# Small_Vitals_2021-03-09.net
KiCad netlist of a schematic drawn in EasyEDA
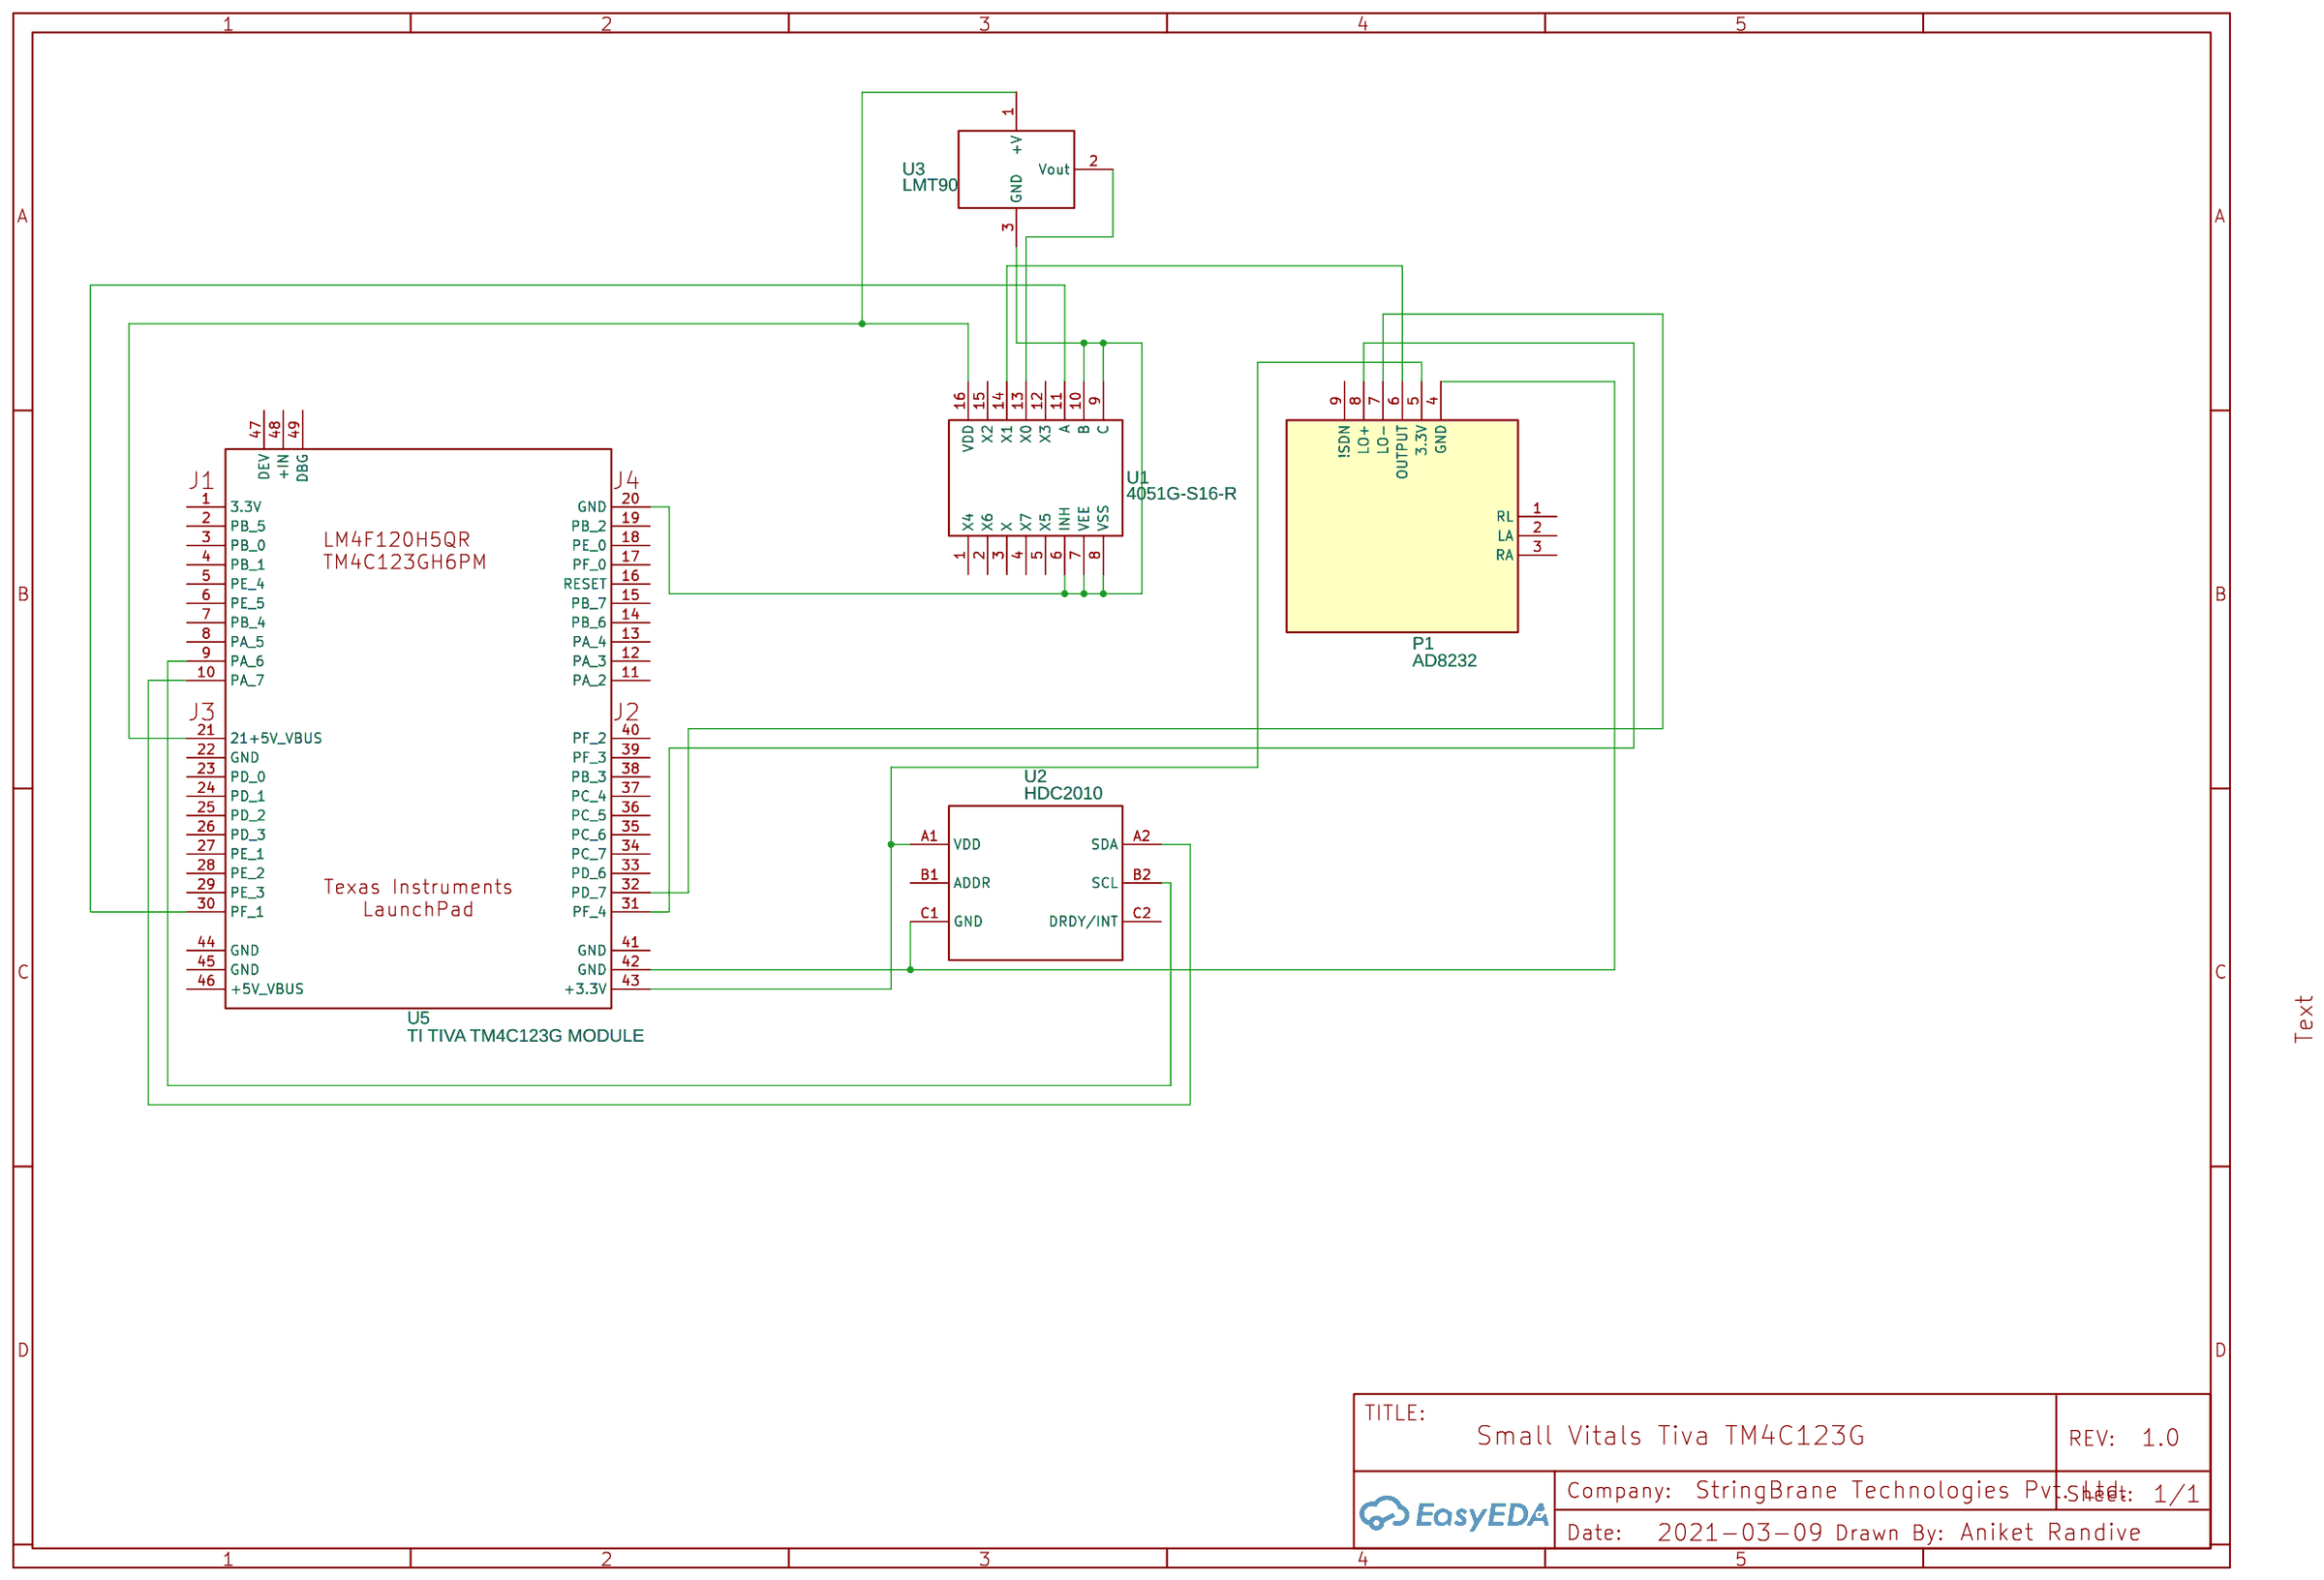
[diagram p0: schematic sheet]

(export (version "E")
  (design (tool "Eeschema 10.0.6"))
  (components
    (comp (ref "P1")
      (value "AD8232")
      (fields (field (name "BOM_Supplier Part") "12587"))
      (libsource (lib "") (part "AD8232"))
    )
    (comp (ref "U1")
      (value "4051G-S16-R")
      (fields (field (name "BOM_Supplier Part") "C73279"))
      (libsource (lib "") (part "4051G-S16-R"))
    )
    (comp (ref "U2") (value "HDC2010") (libsource (lib "") (part "HDC2010")))
    (comp (ref "U3") (value "LMT90") (libsource (lib "") (part "LMT90")))
    (comp (ref "U5") (value "TI TIVA TM4C123G MODULE") (libsource (lib "") (part "TI TIVA TM4C123G MODULE")))
  )
  (nets
    (net (code "1") (name "Net-(P1-3.3V)") (class "Default")
      (node (ref "P1") (pin "5") (pinfunction "3.3V_5") (pintype "unspecified"))
      (node (ref "U2") (pin "A1") (pinfunction "VDD_A1") (pintype "unspecified"))
      (node (ref "U5") (pin "43") (pinfunction "+3.3V_43") (pintype "unspecified"))
    )
    (net (code "2") (name "Net-(P1-GND)") (class "Default")
      (node (ref "P1") (pin "4") (pinfunction "GND_4") (pintype "unspecified"))
      (node (ref "U2") (pin "C1") (pinfunction "GND_C1") (pintype "unspecified"))
      (node (ref "U5") (pin "42") (pinfunction "GND_42") (pintype "unspecified"))
    )
    (net (code "3") (name "Net-(P1-LO+)") (class "Default")
      (node (ref "P1") (pin "8") (pinfunction "LO+_8") (pintype "unspecified"))
      (node (ref "U5") (pin "31") (pinfunction "PF_4_31") (pintype "unspecified"))
    )
    (net (code "4") (name "Net-(P1-LO-)") (class "Default")
      (node (ref "P1") (pin "7") (pinfunction "LO-_7") (pintype "unspecified"))
      (node (ref "U5") (pin "32") (pinfunction "PD_7_32") (pintype "unspecified"))
    )
    (net (code "5") (name "Net-(P1-OUTPUT)") (class "Default")
      (node (ref "P1") (pin "6") (pinfunction "OUTPUT_6") (pintype "unspecified"))
      (node (ref "U1") (pin "14") (pinfunction "X1_14") (pintype "unspecified"))
    )
    (net (code "6") (name "Net-(U1-A)") (class "Default")
      (node (ref "U1") (pin "11") (pinfunction "A_11") (pintype "unspecified"))
      (node (ref "U5") (pin "30") (pinfunction "PF_1_30") (pintype "unspecified"))
    )
    (net (code "7") (name "Net-(U1-B)") (class "Default")
      (node (ref "U1") (pin "10") (pinfunction "B_10") (pintype "unspecified"))
      (node (ref "U1") (pin "6") (pinfunction "INH_6") (pintype "unspecified"))
      (node (ref "U1") (pin "7") (pinfunction "VEE_7") (pintype "unspecified"))
      (node (ref "U1") (pin "8") (pinfunction "VSS_8") (pintype "unspecified"))
      (node (ref "U1") (pin "9") (pinfunction "C_9") (pintype "unspecified"))
      (node (ref "U3") (pin "3") (pinfunction "GND_3") (pintype "unspecified"))
      (node (ref "U5") (pin "20") (pinfunction "GND_20") (pintype "unspecified"))
    )
    (net (code "8") (name "Net-(U1-VDD)") (class "Default")
      (node (ref "U1") (pin "16") (pinfunction "VDD_16") (pintype "unspecified"))
      (node (ref "U3") (pin "1") (pinfunction "+V_1") (pintype "unspecified"))
      (node (ref "U5") (pin "21") (pinfunction "21+5V_VBUS_21") (pintype "unspecified"))
    )
    (net (code "9") (name "Net-(U1-X0)") (class "Default")
      (node (ref "U1") (pin "13") (pinfunction "X0_13") (pintype "unspecified"))
      (node (ref "U3") (pin "2") (pinfunction "Vout_2") (pintype "unspecified"))
    )
    (net (code "10") (name "Net-(U2-SCL)") (class "Default")
      (node (ref "U2") (pin "B2") (pinfunction "SCL_B2") (pintype "unspecified"))
      (node (ref "U5") (pin "9") (pinfunction "PA_6_9") (pintype "unspecified"))
    )
    (net (code "11") (name "Net-(U2-SDA)") (class "Default")
      (node (ref "U2") (pin "A2") (pinfunction "SDA_A2") (pintype "unspecified"))
      (node (ref "U5") (pin "10") (pinfunction "PA_7_10") (pintype "unspecified"))
    )
    (net (code "12") (name "unconnected-(P1-!SDN-Pad9)") (class "Default")
      (node (ref "P1") (pin "9") (pinfunction "!SDN_9") (pintype "unspecified"))
    )
    (net (code "13") (name "unconnected-(P1-LA-Pad2)") (class "Default")
      (node (ref "P1") (pin "2") (pinfunction "LA_2") (pintype "unspecified"))
    )
    (net (code "14") (name "unconnected-(P1-RA-Pad3)") (class "Default")
      (node (ref "P1") (pin "3") (pinfunction "RA_3") (pintype "unspecified"))
    )
    (net (code "15") (name "unconnected-(P1-RL-Pad1)") (class "Default")
      (node (ref "P1") (pin "1") (pinfunction "RL_1") (pintype "unspecified"))
    )
    (net (code "16") (name "unconnected-(U1-X-Pad3)") (class "Default")
      (node (ref "U1") (pin "3") (pinfunction "X_3") (pintype "unspecified"))
    )
    (net (code "17") (name "unconnected-(U1-X2-Pad15)") (class "Default")
      (node (ref "U1") (pin "15") (pinfunction "X2_15") (pintype "unspecified"))
    )
    (net (code "18") (name "unconnected-(U1-X3-Pad12)") (class "Default")
      (node (ref "U1") (pin "12") (pinfunction "X3_12") (pintype "unspecified"))
    )
    (net (code "19") (name "unconnected-(U1-X4-Pad1)") (class "Default")
      (node (ref "U1") (pin "1") (pinfunction "X4_1") (pintype "unspecified"))
    )
    (net (code "20") (name "unconnected-(U1-X5-Pad5)") (class "Default")
      (node (ref "U1") (pin "5") (pinfunction "X5_5") (pintype "unspecified"))
    )
    (net (code "21") (name "unconnected-(U1-X6-Pad2)") (class "Default")
      (node (ref "U1") (pin "2") (pinfunction "X6_2") (pintype "unspecified"))
    )
    (net (code "22") (name "unconnected-(U1-X7-Pad4)") (class "Default")
      (node (ref "U1") (pin "4") (pinfunction "X7_4") (pintype "unspecified"))
    )
    (net (code "23") (name "unconnected-(U2-ADDR-PadB1)") (class "Default")
      (node (ref "U2") (pin "B1") (pinfunction "ADDR_B1") (pintype "unspecified"))
    )
    (net (code "24") (name "unconnected-(U2-DRDY{slash}INT-PadC2)") (class "Default")
      (node (ref "U2") (pin "C2") (pinfunction "DRDY/INT_C2") (pintype "unspecified"))
    )
    (net (code "25") (name "unconnected-(U5-+5V_VBUS-Pad46)") (class "Default")
      (node (ref "U5") (pin "46") (pinfunction "+5V_VBUS_46") (pintype "unspecified"))
    )
    (net (code "26") (name "unconnected-(U5-+IN-Pad48)") (class "Default")
      (node (ref "U5") (pin "48") (pinfunction "+IN_48") (pintype "unspecified"))
    )
    (net (code "27") (name "unconnected-(U5-3.3V-Pad1)") (class "Default")
      (node (ref "U5") (pin "1") (pinfunction "3.3V_1") (pintype "unspecified"))
    )
    (net (code "28") (name "unconnected-(U5-DBG-Pad49)") (class "Default")
      (node (ref "U5") (pin "49") (pinfunction "DBG_49") (pintype "unspecified"))
    )
    (net (code "29") (name "unconnected-(U5-DEV-Pad47)") (class "Default")
      (node (ref "U5") (pin "47") (pinfunction "DEV_47") (pintype "unspecified"))
    )
    (net (code "30") (name "unconnected-(U5-GND-Pad22)") (class "Default")
      (node (ref "U5") (pin "22") (pinfunction "GND_22") (pintype "unspecified"))
    )
    (net (code "31") (name "unconnected-(U5-GND-Pad41)") (class "Default")
      (node (ref "U5") (pin "41") (pinfunction "GND_41") (pintype "unspecified"))
    )
    (net (code "32") (name "unconnected-(U5-GND-Pad44)") (class "Default")
      (node (ref "U5") (pin "44") (pinfunction "GND_44") (pintype "unspecified"))
    )
    (net (code "33") (name "unconnected-(U5-GND-Pad45)") (class "Default")
      (node (ref "U5") (pin "45") (pinfunction "GND_45") (pintype "unspecified"))
    )
    (net (code "34") (name "unconnected-(U5-PA_2-Pad11)") (class "Default")
      (node (ref "U5") (pin "11") (pinfunction "PA_2_11") (pintype "unspecified"))
    )
    (net (code "35") (name "unconnected-(U5-PA_3-Pad12)") (class "Default")
      (node (ref "U5") (pin "12") (pinfunction "PA_3_12") (pintype "unspecified"))
    )
    (net (code "36") (name "unconnected-(U5-PA_4-Pad13)") (class "Default")
      (node (ref "U5") (pin "13") (pinfunction "PA_4_13") (pintype "unspecified"))
    )
    (net (code "37") (name "unconnected-(U5-PA_5-Pad8)") (class "Default")
      (node (ref "U5") (pin "8") (pinfunction "PA_5_8") (pintype "unspecified"))
    )
    (net (code "38") (name "unconnected-(U5-PB_0-Pad3)") (class "Default")
      (node (ref "U5") (pin "3") (pinfunction "PB_0_3") (pintype "unspecified"))
    )
    (net (code "39") (name "unconnected-(U5-PB_1-Pad4)") (class "Default")
      (node (ref "U5") (pin "4") (pinfunction "PB_1_4") (pintype "unspecified"))
    )
    (net (code "40") (name "unconnected-(U5-PB_2-Pad19)") (class "Default")
      (node (ref "U5") (pin "19") (pinfunction "PB_2_19") (pintype "unspecified"))
    )
    (net (code "41") (name "unconnected-(U5-PB_3-Pad38)") (class "Default")
      (node (ref "U5") (pin "38") (pinfunction "PB_3_38") (pintype "unspecified"))
    )
    (net (code "42") (name "unconnected-(U5-PB_4-Pad7)") (class "Default")
      (node (ref "U5") (pin "7") (pinfunction "PB_4_7") (pintype "unspecified"))
    )
    (net (code "43") (name "unconnected-(U5-PB_5-Pad2)") (class "Default")
      (node (ref "U5") (pin "2") (pinfunction "PB_5_2") (pintype "unspecified"))
    )
    (net (code "44") (name "unconnected-(U5-PB_6-Pad14)") (class "Default")
      (node (ref "U5") (pin "14") (pinfunction "PB_6_14") (pintype "unspecified"))
    )
    (net (code "45") (name "unconnected-(U5-PB_7-Pad15)") (class "Default")
      (node (ref "U5") (pin "15") (pinfunction "PB_7_15") (pintype "unspecified"))
    )
    (net (code "46") (name "unconnected-(U5-PC_4-Pad37)") (class "Default")
      (node (ref "U5") (pin "37") (pinfunction "PC_4_37") (pintype "unspecified"))
    )
    (net (code "47") (name "unconnected-(U5-PC_5-Pad36)") (class "Default")
      (node (ref "U5") (pin "36") (pinfunction "PC_5_36") (pintype "unspecified"))
    )
    (net (code "48") (name "unconnected-(U5-PC_6-Pad35)") (class "Default")
      (node (ref "U5") (pin "35") (pinfunction "PC_6_35") (pintype "unspecified"))
    )
    (net (code "49") (name "unconnected-(U5-PC_7-Pad34)") (class "Default")
      (node (ref "U5") (pin "34") (pinfunction "PC_7_34") (pintype "unspecified"))
    )
    (net (code "50") (name "unconnected-(U5-PD_0-Pad23)") (class "Default")
      (node (ref "U5") (pin "23") (pinfunction "PD_0_23") (pintype "unspecified"))
    )
    (net (code "51") (name "unconnected-(U5-PD_1-Pad24)") (class "Default")
      (node (ref "U5") (pin "24") (pinfunction "PD_1_24") (pintype "unspecified"))
    )
    (net (code "52") (name "unconnected-(U5-PD_2-Pad25)") (class "Default")
      (node (ref "U5") (pin "25") (pinfunction "PD_2_25") (pintype "unspecified"))
    )
    (net (code "53") (name "unconnected-(U5-PD_3-Pad26)") (class "Default")
      (node (ref "U5") (pin "26") (pinfunction "PD_3_26") (pintype "unspecified"))
    )
    (net (code "54") (name "unconnected-(U5-PD_6-Pad33)") (class "Default")
      (node (ref "U5") (pin "33") (pinfunction "PD_6_33") (pintype "unspecified"))
    )
    (net (code "55") (name "unconnected-(U5-PE_0-Pad18)") (class "Default")
      (node (ref "U5") (pin "18") (pinfunction "PE_0_18") (pintype "unspecified"))
    )
    (net (code "56") (name "unconnected-(U5-PE_1-Pad27)") (class "Default")
      (node (ref "U5") (pin "27") (pinfunction "PE_1_27") (pintype "unspecified"))
    )
    (net (code "57") (name "unconnected-(U5-PE_2-Pad28)") (class "Default")
      (node (ref "U5") (pin "28") (pinfunction "PE_2_28") (pintype "unspecified"))
    )
    (net (code "58") (name "unconnected-(U5-PE_3-Pad29)") (class "Default")
      (node (ref "U5") (pin "29") (pinfunction "PE_3_29") (pintype "unspecified"))
    )
    (net (code "59") (name "unconnected-(U5-PE_4-Pad5)") (class "Default")
      (node (ref "U5") (pin "5") (pinfunction "PE_4_5") (pintype "unspecified"))
    )
    (net (code "60") (name "unconnected-(U5-PE_5-Pad6)") (class "Default")
      (node (ref "U5") (pin "6") (pinfunction "PE_5_6") (pintype "unspecified"))
    )
    (net (code "61") (name "unconnected-(U5-PF_0-Pad17)") (class "Default")
      (node (ref "U5") (pin "17") (pinfunction "PF_0_17") (pintype "unspecified"))
    )
    (net (code "62") (name "unconnected-(U5-PF_2-Pad40)") (class "Default")
      (node (ref "U5") (pin "40") (pinfunction "PF_2_40") (pintype "unspecified"))
    )
    (net (code "63") (name "unconnected-(U5-PF_3-Pad39)") (class "Default")
      (node (ref "U5") (pin "39") (pinfunction "PF_3_39") (pintype "unspecified"))
    )
    (net (code "64") (name "unconnected-(U5-RESET-Pad16)") (class "Default")
      (node (ref "U5") (pin "16") (pinfunction "RESET_16") (pintype "unspecified"))
    )
  )
)
